# elevator_iopanel_revA.net
KiCad netlist of a schematic drawn in EAGLE
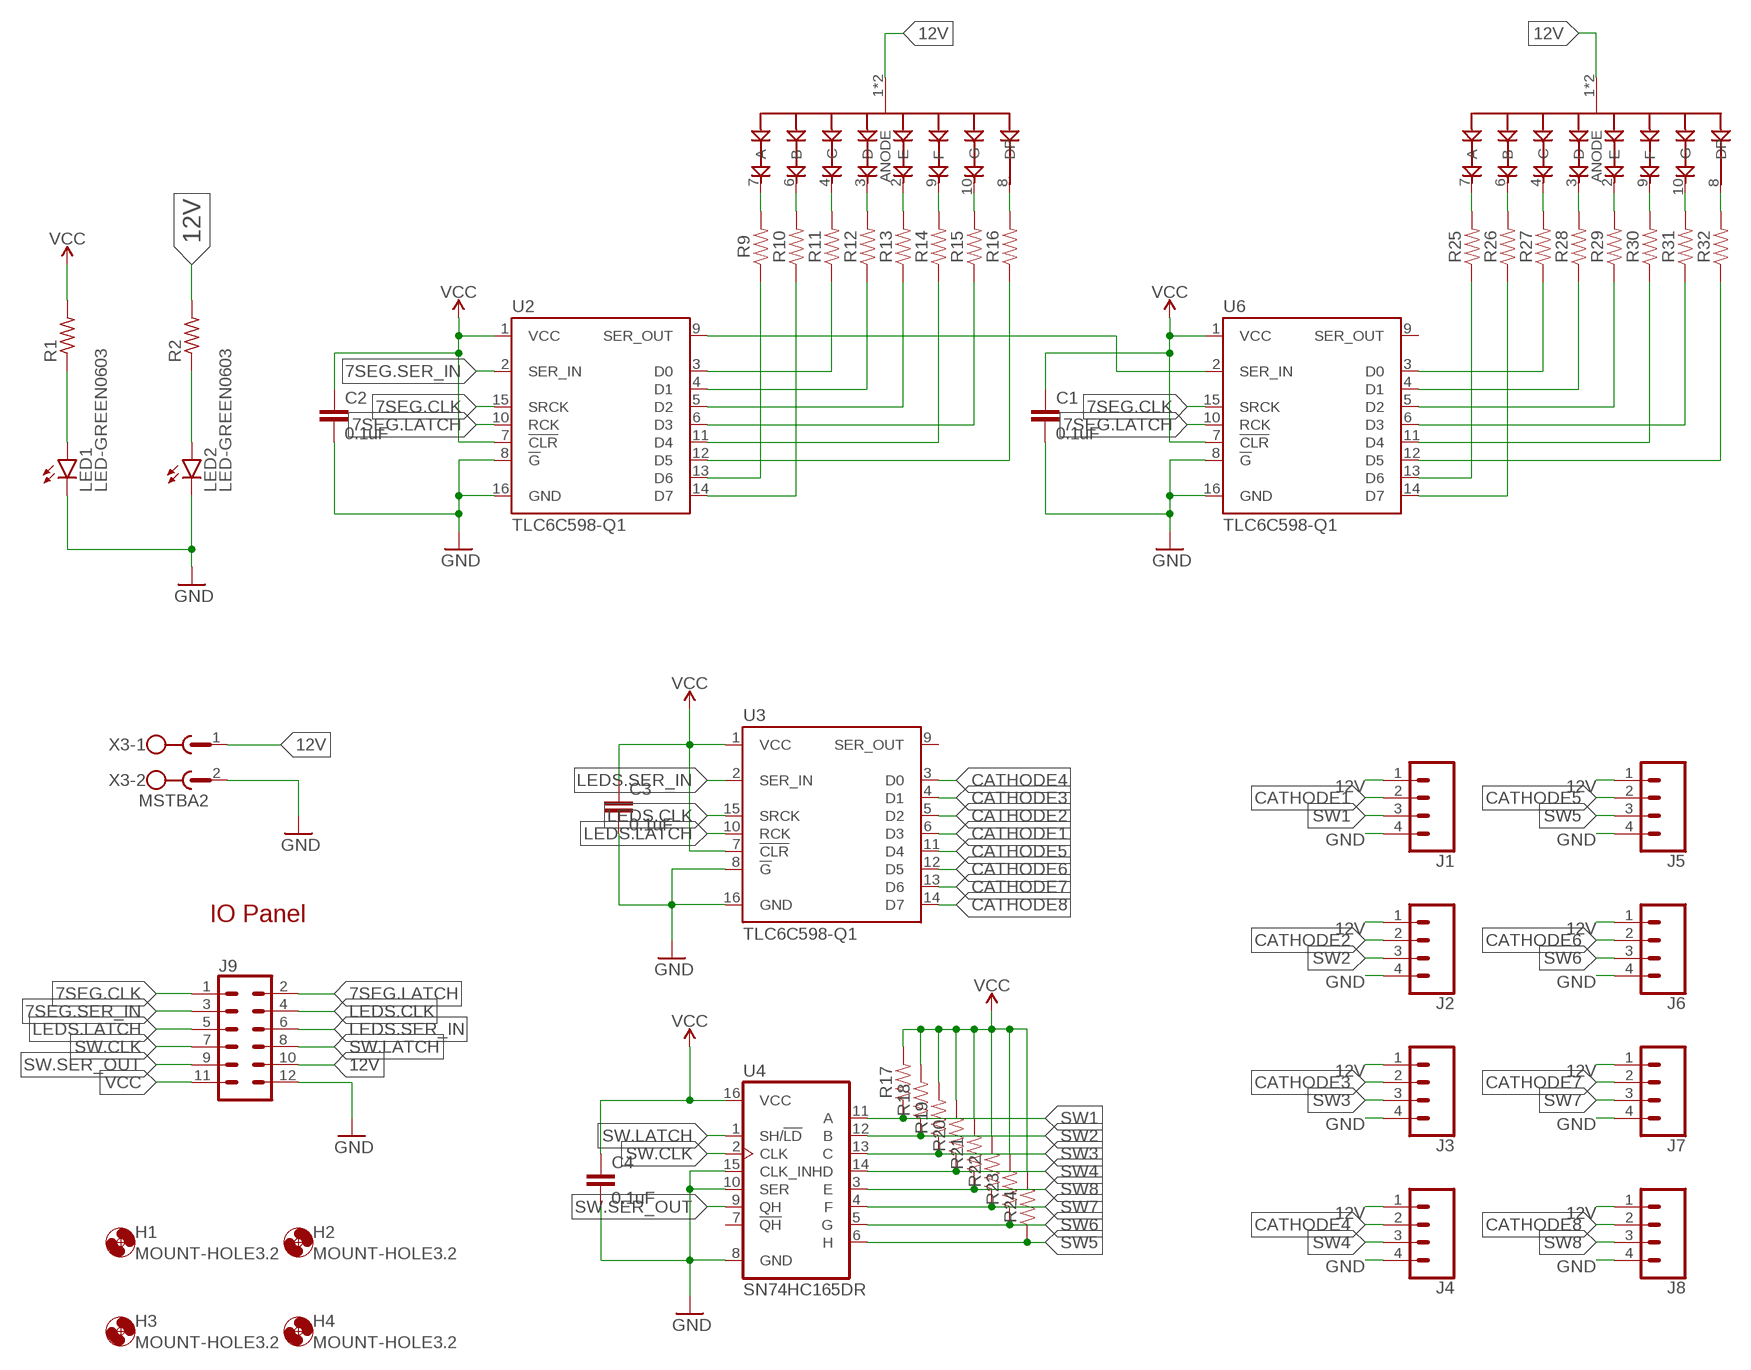
[diagram p0: schematic, sheet 1]

(export (version "E")
  (design (tool "Eeschema 10.0.6"))
  (components
    (comp (ref "C1")
      (value "0.1uF")
      (footprint "eagle-import:0603")
      (libsource (lib "eagle-import") (part "0.1UF-0603-25V-5%"))
    )
    (comp (ref "C2")
      (value "0.1uF")
      (footprint "eagle-import:0603")
      (libsource (lib "eagle-import") (part "0.1UF-0603-25V-5%"))
    )
    (comp (ref "C3")
      (value "0.1uF")
      (footprint "eagle-import:0603")
      (libsource (lib "eagle-import") (part "0.1UF-0603-25V-5%"))
    )
    (comp (ref "C4")
      (value "0.1uF")
      (footprint "eagle-import:0603")
      (libsource (lib "eagle-import") (part "0.1UF-0603-25V-5%"))
    )
    (comp (ref "D2")
      (value "SA15-11EWA")
      (footprint "eagle-import:SA15-11EWA")
      (libsource (lib "eagle-import") (part "SA15-11EWA"))
    )
    (comp (ref "D4")
      (value "SA15-11EWA")
      (footprint "eagle-import:SA15-11EWA")
      (libsource (lib "eagle-import") (part "SA15-11EWA"))
    )
    (comp (ref "H1")
      (value "MOUNT-HOLE3.2")
      (footprint "eagle-import:3,2")
      (libsource (lib "eagle-import") (part "MOUNT-HOLE3.2"))
    )
    (comp (ref "H2")
      (value "MOUNT-HOLE3.2")
      (footprint "eagle-import:3,2")
      (libsource (lib "eagle-import") (part "MOUNT-HOLE3.2"))
    )
    (comp (ref "H3")
      (value "MOUNT-HOLE3.2")
      (footprint "eagle-import:3,2")
      (libsource (lib "eagle-import") (part "MOUNT-HOLE3.2"))
    )
    (comp (ref "H4")
      (value "MOUNT-HOLE3.2")
      (footprint "eagle-import:3,2")
      (libsource (lib "eagle-import") (part "MOUNT-HOLE3.2"))
    )
    (comp (ref "J1")
      (value "CONN_04LONGPADS")
      (footprint "eagle-import:1X04_LONGPADS")
      (libsource (lib "eagle-import") (part "CONN_04LONGPADS"))
    )
    (comp (ref "J2")
      (value "CONN_04LONGPADS")
      (footprint "eagle-import:1X04_LONGPADS")
      (libsource (lib "eagle-import") (part "CONN_04LONGPADS"))
    )
    (comp (ref "J3")
      (value "CONN_04LONGPADS")
      (footprint "eagle-import:1X04_LONGPADS")
      (libsource (lib "eagle-import") (part "CONN_04LONGPADS"))
    )
    (comp (ref "J4")
      (value "CONN_04LONGPADS")
      (footprint "eagle-import:1X04_LONGPADS")
      (libsource (lib "eagle-import") (part "CONN_04LONGPADS"))
    )
    (comp (ref "J5")
      (value "CONN_04LONGPADS")
      (footprint "eagle-import:1X04_LONGPADS")
      (libsource (lib "eagle-import") (part "CONN_04LONGPADS"))
    )
    (comp (ref "J6")
      (value "CONN_04LONGPADS")
      (footprint "eagle-import:1X04_LONGPADS")
      (libsource (lib "eagle-import") (part "CONN_04LONGPADS"))
    )
    (comp (ref "J7")
      (value "CONN_04LONGPADS")
      (footprint "eagle-import:1X04_LONGPADS")
      (libsource (lib "eagle-import") (part "CONN_04LONGPADS"))
    )
    (comp (ref "J8")
      (value "CONN_04LONGPADS")
      (footprint "eagle-import:1X04_LONGPADS")
      (libsource (lib "eagle-import") (part "CONN_04LONGPADS"))
    )
    (comp (ref "J9")
      (value "CONN_06X22X6SHR")
      (footprint "eagle-import:2X6-SHROUDED")
      (libsource (lib "eagle-import") (part "CONN_06X22X6SHR"))
    )
    (comp (ref "LED1")
      (value "LED-GREEN0603")
      (footprint "eagle-import:0603-GREEN")
      (libsource (lib "eagle-import") (part "LED-GREEN0603"))
    )
    (comp (ref "LED2")
      (value "LED-GREEN0603")
      (footprint "eagle-import:0603-GREEN")
      (libsource (lib "eagle-import") (part "LED-GREEN0603"))
    )
    (comp (ref "R1")
      (value "R-US_R0603")
      (footprint "eagle-import:R0603")
      (libsource (lib "eagle-import") (part "R-US_R0603"))
    )
    (comp (ref "R2")
      (value "R-US_R0603")
      (footprint "eagle-import:R0603")
      (libsource (lib "eagle-import") (part "R-US_R0603"))
    )
    (comp (ref "R9")
      (value "20KOHM-0603-1/10W-1%")
      (footprint "eagle-import:0603")
      (libsource (lib "eagle-import") (part "20KOHM-0603-1/10W-1%"))
    )
    (comp (ref "R10")
      (value "20KOHM-0603-1/10W-1%")
      (footprint "eagle-import:0603")
      (libsource (lib "eagle-import") (part "20KOHM-0603-1/10W-1%"))
    )
    (comp (ref "R11")
      (value "20KOHM-0603-1/10W-1%")
      (footprint "eagle-import:0603")
      (libsource (lib "eagle-import") (part "20KOHM-0603-1/10W-1%"))
    )
    (comp (ref "R12")
      (value "20KOHM-0603-1/10W-1%")
      (footprint "eagle-import:0603")
      (libsource (lib "eagle-import") (part "20KOHM-0603-1/10W-1%"))
    )
    (comp (ref "R13")
      (value "20KOHM-0603-1/10W-1%")
      (footprint "eagle-import:0603")
      (libsource (lib "eagle-import") (part "20KOHM-0603-1/10W-1%"))
    )
    (comp (ref "R14")
      (value "20KOHM-0603-1/10W-1%")
      (footprint "eagle-import:0603")
      (libsource (lib "eagle-import") (part "20KOHM-0603-1/10W-1%"))
    )
    (comp (ref "R15")
      (value "20KOHM-0603-1/10W-1%")
      (footprint "eagle-import:0603")
      (libsource (lib "eagle-import") (part "20KOHM-0603-1/10W-1%"))
    )
    (comp (ref "R16")
      (value "20KOHM-0603-1/10W-1%")
      (footprint "eagle-import:0603")
      (libsource (lib "eagle-import") (part "20KOHM-0603-1/10W-1%"))
    )
    (comp (ref "R17")
      (value "20KOHM-0603-1/10W-1%")
      (footprint "eagle-import:0603")
      (libsource (lib "eagle-import") (part "20KOHM-0603-1/10W-1%"))
    )
    (comp (ref "R18")
      (value "20KOHM-0603-1/10W-1%")
      (footprint "eagle-import:0603")
      (libsource (lib "eagle-import") (part "20KOHM-0603-1/10W-1%"))
    )
    (comp (ref "R19")
      (value "20KOHM-0603-1/10W-1%")
      (footprint "eagle-import:0603")
      (libsource (lib "eagle-import") (part "20KOHM-0603-1/10W-1%"))
    )
    (comp (ref "R20")
      (value "20KOHM-0603-1/10W-1%")
      (footprint "eagle-import:0603")
      (libsource (lib "eagle-import") (part "20KOHM-0603-1/10W-1%"))
    )
    (comp (ref "R21")
      (value "20KOHM-0603-1/10W-1%")
      (footprint "eagle-import:0603")
      (libsource (lib "eagle-import") (part "20KOHM-0603-1/10W-1%"))
    )
    (comp (ref "R22")
      (value "20KOHM-0603-1/10W-1%")
      (footprint "eagle-import:0603")
      (libsource (lib "eagle-import") (part "20KOHM-0603-1/10W-1%"))
    )
    (comp (ref "R23")
      (value "20KOHM-0603-1/10W-1%")
      (footprint "eagle-import:0603")
      (libsource (lib "eagle-import") (part "20KOHM-0603-1/10W-1%"))
    )
    (comp (ref "R24")
      (value "20KOHM-0603-1/10W-1%")
      (footprint "eagle-import:0603")
      (libsource (lib "eagle-import") (part "20KOHM-0603-1/10W-1%"))
    )
    (comp (ref "R25")
      (value "20KOHM-0603-1/10W-1%")
      (footprint "eagle-import:0603")
      (libsource (lib "eagle-import") (part "20KOHM-0603-1/10W-1%"))
    )
    (comp (ref "R26")
      (value "20KOHM-0603-1/10W-1%")
      (footprint "eagle-import:0603")
      (libsource (lib "eagle-import") (part "20KOHM-0603-1/10W-1%"))
    )
    (comp (ref "R27")
      (value "20KOHM-0603-1/10W-1%")
      (footprint "eagle-import:0603")
      (libsource (lib "eagle-import") (part "20KOHM-0603-1/10W-1%"))
    )
    (comp (ref "R28")
      (value "20KOHM-0603-1/10W-1%")
      (footprint "eagle-import:0603")
      (libsource (lib "eagle-import") (part "20KOHM-0603-1/10W-1%"))
    )
    (comp (ref "R29")
      (value "20KOHM-0603-1/10W-1%")
      (footprint "eagle-import:0603")
      (libsource (lib "eagle-import") (part "20KOHM-0603-1/10W-1%"))
    )
    (comp (ref "R30")
      (value "20KOHM-0603-1/10W-1%")
      (footprint "eagle-import:0603")
      (libsource (lib "eagle-import") (part "20KOHM-0603-1/10W-1%"))
    )
    (comp (ref "R31")
      (value "20KOHM-0603-1/10W-1%")
      (footprint "eagle-import:0603")
      (libsource (lib "eagle-import") (part "20KOHM-0603-1/10W-1%"))
    )
    (comp (ref "R32")
      (value "20KOHM-0603-1/10W-1%")
      (footprint "eagle-import:0603")
      (libsource (lib "eagle-import") (part "20KOHM-0603-1/10W-1%"))
    )
    (comp (ref "U2")
      (value "TLC6C598-Q1")
      (footprint "eagle-import:SO16")
      (libsource (lib "eagle-import") (part "TPIC6C596SOIC"))
    )
    (comp (ref "U3")
      (value "TLC6C598-Q1")
      (footprint "eagle-import:SO16")
      (libsource (lib "eagle-import") (part "TPIC6C596SOIC"))
    )
    (comp (ref "U4")
      (value "SN74HC165DR")
      (footprint "eagle-import:SO16")
      (libsource (lib "eagle-import") (part "74165DHC"))
    )
    (comp (ref "U6")
      (value "TLC6C598-Q1")
      (footprint "eagle-import:SO16")
      (libsource (lib "eagle-import") (part "TPIC6C596SOIC"))
    )
    (comp (ref "X3")
      (value "MSTBA2")
      (footprint "eagle-import:MSTBA2")
      (fields (field (name "MF") "FARNELL") (field (name "MPN") "1757242"))
      (libsource (lib "eagle-import") (part "MSTBA2"))
    )
  )
  (nets
    (net (code "1") (name "7SEG.CLK") (class "Default")
      (node (ref "J9") (pin "1") (pinfunction "1_1") (pintype "passive"))
      (node (ref "U2") (pin "15") (pinfunction "SRCK_15") (pintype "input"))
      (node (ref "U6") (pin "15") (pinfunction "SRCK_15") (pintype "input"))
    )
    (net (code "2") (name "7SEG.LATCH") (class "Default")
      (node (ref "J9") (pin "2") (pinfunction "2_2") (pintype "passive"))
      (node (ref "U2") (pin "10") (pinfunction "RCK_10") (pintype "input"))
      (node (ref "U6") (pin "10") (pinfunction "RCK_10") (pintype "input"))
    )
    (net (code "3") (name "7SEG.SER_IN") (class "Default")
      (node (ref "J9") (pin "3") (pinfunction "3_3") (pintype "passive"))
      (node (ref "U2") (pin "2") (pinfunction "SER_IN_2") (pintype "input"))
    )
    (net (code "4") (name "12V") (class "Default")
      (node (ref "D2") (pin "1") (pinfunction "ANODE_1") (pintype "bidirectional"))
      (node (ref "D2") (pin "5") (pinfunction "ANODE_5") (pintype "bidirectional"))
      (node (ref "D4") (pin "1") (pinfunction "ANODE_1") (pintype "bidirectional"))
      (node (ref "D4") (pin "5") (pinfunction "ANODE_5") (pintype "bidirectional"))
      (node (ref "J1") (pin "1") (pinfunction "1_1") (pintype "passive"))
      (node (ref "J2") (pin "1") (pinfunction "1_1") (pintype "passive"))
      (node (ref "J3") (pin "1") (pinfunction "1_1") (pintype "passive"))
      (node (ref "J4") (pin "1") (pinfunction "1_1") (pintype "passive"))
      (node (ref "J5") (pin "1") (pinfunction "1_1") (pintype "passive"))
      (node (ref "J6") (pin "1") (pinfunction "1_1") (pintype "passive"))
      (node (ref "J7") (pin "1") (pinfunction "1_1") (pintype "passive"))
      (node (ref "J8") (pin "1") (pinfunction "1_1") (pintype "passive"))
      (node (ref "J9") (pin "10") (pinfunction "10_10") (pintype "passive"))
      (node (ref "R2") (pin "2") (pinfunction "2_2") (pintype "passive"))
      (node (ref "X3") (pin "1") (pinfunction "1_1") (pintype "passive"))
    )
    (net (code "5") (name "CATHODE1") (class "Default")
      (node (ref "J1") (pin "2") (pinfunction "2_2") (pintype "passive"))
      (node (ref "U3") (pin "6") (pinfunction "D3_6") (pintype "output"))
    )
    (net (code "6") (name "CATHODE2") (class "Default")
      (node (ref "J2") (pin "2") (pinfunction "2_2") (pintype "passive"))
      (node (ref "U3") (pin "5") (pinfunction "D2_5") (pintype "output"))
    )
    (net (code "7") (name "CATHODE3") (class "Default")
      (node (ref "J3") (pin "2") (pinfunction "2_2") (pintype "passive"))
      (node (ref "U3") (pin "4") (pinfunction "D1_4") (pintype "output"))
    )
    (net (code "8") (name "CATHODE4") (class "Default")
      (node (ref "J4") (pin "2") (pinfunction "2_2") (pintype "passive"))
      (node (ref "U3") (pin "3") (pinfunction "D0_3") (pintype "output"))
    )
    (net (code "9") (name "CATHODE5") (class "Default")
      (node (ref "J5") (pin "2") (pinfunction "2_2") (pintype "passive"))
      (node (ref "U3") (pin "11") (pinfunction "D4_11") (pintype "output"))
    )
    (net (code "10") (name "CATHODE6") (class "Default")
      (node (ref "J6") (pin "2") (pinfunction "2_2") (pintype "passive"))
      (node (ref "U3") (pin "12") (pinfunction "D5_12") (pintype "output"))
    )
    (net (code "11") (name "CATHODE7") (class "Default")
      (node (ref "J7") (pin "2") (pinfunction "2_2") (pintype "passive"))
      (node (ref "U3") (pin "13") (pinfunction "D6_13") (pintype "output"))
    )
    (net (code "12") (name "CATHODE8") (class "Default")
      (node (ref "J8") (pin "2") (pinfunction "2_2") (pintype "passive"))
      (node (ref "U3") (pin "14") (pinfunction "D7_14") (pintype "output"))
    )
    (net (code "13") (name "GND") (class "Default")
      (node (ref "C1") (pin "2") (pinfunction "2_2") (pintype "passive"))
      (node (ref "C2") (pin "2") (pinfunction "2_2") (pintype "passive"))
      (node (ref "C3") (pin "2") (pinfunction "2_2") (pintype "passive"))
      (node (ref "C4") (pin "2") (pinfunction "2_2") (pintype "passive"))
      (node (ref "J1") (pin "4") (pinfunction "4_4") (pintype "passive"))
      (node (ref "J2") (pin "4") (pinfunction "4_4") (pintype "passive"))
      (node (ref "J3") (pin "4") (pinfunction "4_4") (pintype "passive"))
      (node (ref "J4") (pin "4") (pinfunction "4_4") (pintype "passive"))
      (node (ref "J5") (pin "4") (pinfunction "4_4") (pintype "passive"))
      (node (ref "J6") (pin "4") (pinfunction "4_4") (pintype "passive"))
      (node (ref "J7") (pin "4") (pinfunction "4_4") (pintype "passive"))
      (node (ref "J8") (pin "4") (pinfunction "4_4") (pintype "passive"))
      (node (ref "J9") (pin "12") (pinfunction "12_12") (pintype "passive"))
      (node (ref "LED1") (pin "C") (pinfunction "C_C") (pintype "passive"))
      (node (ref "LED2") (pin "C") (pinfunction "C_C") (pintype "passive"))
      (node (ref "U2") (pin "16") (pinfunction "GND_16") (pintype "power_in"))
      (node (ref "U2") (pin "8") (pinfunction "~{G}_8") (pintype "input"))
      (node (ref "U3") (pin "16") (pinfunction "GND_16") (pintype "power_in"))
      (node (ref "U3") (pin "8") (pinfunction "~{G}_8") (pintype "input"))
      (node (ref "U4") (pin "10") (pinfunction "SER_10") (pintype "input"))
      (node (ref "U4") (pin "15") (pinfunction "CLK_INH_15") (pintype "input"))
      (node (ref "U4") (pin "8") (pinfunction "GND_8") (pintype "power_in"))
      (node (ref "U6") (pin "16") (pinfunction "GND_16") (pintype "power_in"))
      (node (ref "U6") (pin "8") (pinfunction "~{G}_8") (pintype "input"))
      (node (ref "X3") (pin "2") (pinfunction "1_2") (pintype "passive"))
    )
    (net (code "14") (name "LEDS.CLK") (class "Default")
      (node (ref "J9") (pin "4") (pinfunction "4_4") (pintype "passive"))
      (node (ref "U3") (pin "15") (pinfunction "SRCK_15") (pintype "input"))
    )
    (net (code "15") (name "LEDS.LATCH") (class "Default")
      (node (ref "J9") (pin "5") (pinfunction "5_5") (pintype "passive"))
      (node (ref "U3") (pin "10") (pinfunction "RCK_10") (pintype "input"))
    )
    (net (code "16") (name "LEDS.SER_IN") (class "Default")
      (node (ref "J9") (pin "6") (pinfunction "6_6") (pintype "passive"))
      (node (ref "U3") (pin "2") (pinfunction "SER_IN_2") (pintype "input"))
    )
    (net (code "17") (name "Net-(D2-A)") (class "Default")
      (node (ref "D2") (pin "7") (pinfunction "A_7") (pintype "bidirectional"))
      (node (ref "R9") (pin "2") (pinfunction "2_2") (pintype "passive"))
    )
    (net (code "18") (name "Net-(D2-B)") (class "Default")
      (node (ref "D2") (pin "6") (pinfunction "B_6") (pintype "bidirectional"))
      (node (ref "R10") (pin "2") (pinfunction "2_2") (pintype "passive"))
    )
    (net (code "19") (name "Net-(D2-C)") (class "Default")
      (node (ref "D2") (pin "4") (pinfunction "C_4") (pintype "bidirectional"))
      (node (ref "R11") (pin "2") (pinfunction "2_2") (pintype "passive"))
    )
    (net (code "20") (name "Net-(D2-D)") (class "Default")
      (node (ref "D2") (pin "3") (pinfunction "D_3") (pintype "bidirectional"))
      (node (ref "R12") (pin "2") (pinfunction "2_2") (pintype "passive"))
    )
    (net (code "21") (name "Net-(D2-DP)") (class "Default")
      (node (ref "D2") (pin "8") (pinfunction "DP_8") (pintype "bidirectional"))
      (node (ref "R16") (pin "2") (pinfunction "2_2") (pintype "passive"))
    )
    (net (code "22") (name "Net-(D2-E)") (class "Default")
      (node (ref "D2") (pin "2") (pinfunction "E_2") (pintype "bidirectional"))
      (node (ref "R13") (pin "2") (pinfunction "2_2") (pintype "passive"))
    )
    (net (code "23") (name "Net-(D2-F)") (class "Default")
      (node (ref "D2") (pin "9") (pinfunction "F_9") (pintype "bidirectional"))
      (node (ref "R14") (pin "2") (pinfunction "2_2") (pintype "passive"))
    )
    (net (code "24") (name "Net-(D2-G)") (class "Default")
      (node (ref "D2") (pin "10") (pinfunction "G_10") (pintype "bidirectional"))
      (node (ref "R15") (pin "2") (pinfunction "2_2") (pintype "passive"))
    )
    (net (code "25") (name "Net-(D4-A)") (class "Default")
      (node (ref "D4") (pin "7") (pinfunction "A_7") (pintype "bidirectional"))
      (node (ref "R25") (pin "2") (pinfunction "2_2") (pintype "passive"))
    )
    (net (code "26") (name "Net-(D4-B)") (class "Default")
      (node (ref "D4") (pin "6") (pinfunction "B_6") (pintype "bidirectional"))
      (node (ref "R26") (pin "2") (pinfunction "2_2") (pintype "passive"))
    )
    (net (code "27") (name "Net-(D4-C)") (class "Default")
      (node (ref "D4") (pin "4") (pinfunction "C_4") (pintype "bidirectional"))
      (node (ref "R27") (pin "2") (pinfunction "2_2") (pintype "passive"))
    )
    (net (code "28") (name "Net-(D4-D)") (class "Default")
      (node (ref "D4") (pin "3") (pinfunction "D_3") (pintype "bidirectional"))
      (node (ref "R28") (pin "2") (pinfunction "2_2") (pintype "passive"))
    )
    (net (code "29") (name "Net-(D4-DP)") (class "Default")
      (node (ref "D4") (pin "8") (pinfunction "DP_8") (pintype "bidirectional"))
      (node (ref "R32") (pin "2") (pinfunction "2_2") (pintype "passive"))
    )
    (net (code "30") (name "Net-(D4-E)") (class "Default")
      (node (ref "D4") (pin "2") (pinfunction "E_2") (pintype "bidirectional"))
      (node (ref "R29") (pin "2") (pinfunction "2_2") (pintype "passive"))
    )
    (net (code "31") (name "Net-(D4-F)") (class "Default")
      (node (ref "D4") (pin "9") (pinfunction "F_9") (pintype "bidirectional"))
      (node (ref "R30") (pin "2") (pinfunction "2_2") (pintype "passive"))
    )
    (net (code "32") (name "Net-(D4-G)") (class "Default")
      (node (ref "D4") (pin "10") (pinfunction "G_10") (pintype "bidirectional"))
      (node (ref "R31") (pin "2") (pinfunction "2_2") (pintype "passive"))
    )
    (net (code "33") (name "Net-(LED1-PadA)") (class "Default")
      (node (ref "LED1") (pin "A") (pinfunction "A_A") (pintype "passive"))
      (node (ref "R1") (pin "1") (pinfunction "1_1") (pintype "passive"))
    )
    (net (code "34") (name "Net-(LED2-PadA)") (class "Default")
      (node (ref "LED2") (pin "A") (pinfunction "A_A") (pintype "passive"))
      (node (ref "R2") (pin "1") (pinfunction "1_1") (pintype "passive"))
    )
    (net (code "35") (name "Net-(U2-D0)") (class "Default")
      (node (ref "R11") (pin "1") (pinfunction "1_1") (pintype "passive"))
      (node (ref "U2") (pin "3") (pinfunction "D0_3") (pintype "output"))
    )
    (net (code "36") (name "Net-(U2-D1)") (class "Default")
      (node (ref "R12") (pin "1") (pinfunction "1_1") (pintype "passive"))
      (node (ref "U2") (pin "4") (pinfunction "D1_4") (pintype "output"))
    )
    (net (code "37") (name "Net-(U2-D2)") (class "Default")
      (node (ref "R13") (pin "1") (pinfunction "1_1") (pintype "passive"))
      (node (ref "U2") (pin "5") (pinfunction "D2_5") (pintype "output"))
    )
    (net (code "38") (name "Net-(U2-D3)") (class "Default")
      (node (ref "R15") (pin "1") (pinfunction "1_1") (pintype "passive"))
      (node (ref "U2") (pin "6") (pinfunction "D3_6") (pintype "output"))
    )
    (net (code "39") (name "Net-(U2-D4)") (class "Default")
      (node (ref "R14") (pin "1") (pinfunction "1_1") (pintype "passive"))
      (node (ref "U2") (pin "11") (pinfunction "D4_11") (pintype "output"))
    )
    (net (code "40") (name "Net-(U2-D5)") (class "Default")
      (node (ref "R16") (pin "1") (pinfunction "1_1") (pintype "passive"))
      (node (ref "U2") (pin "12") (pinfunction "D5_12") (pintype "output"))
    )
    (net (code "41") (name "Net-(U2-D6)") (class "Default")
      (node (ref "R9") (pin "1") (pinfunction "1_1") (pintype "passive"))
      (node (ref "U2") (pin "13") (pinfunction "D6_13") (pintype "output"))
    )
    (net (code "42") (name "Net-(U2-D7)") (class "Default")
      (node (ref "R10") (pin "1") (pinfunction "1_1") (pintype "passive"))
      (node (ref "U2") (pin "14") (pinfunction "D7_14") (pintype "output"))
    )
    (net (code "43") (name "Net-(U2-SER_OUT)") (class "Default")
      (node (ref "U2") (pin "9") (pinfunction "SER_OUT_9") (pintype "output"))
      (node (ref "U6") (pin "2") (pinfunction "SER_IN_2") (pintype "input"))
    )
    (net (code "44") (name "Net-(U6-D0)") (class "Default")
      (node (ref "R27") (pin "1") (pinfunction "1_1") (pintype "passive"))
      (node (ref "U6") (pin "3") (pinfunction "D0_3") (pintype "output"))
    )
    (net (code "45") (name "Net-(U6-D1)") (class "Default")
      (node (ref "R28") (pin "1") (pinfunction "1_1") (pintype "passive"))
      (node (ref "U6") (pin "4") (pinfunction "D1_4") (pintype "output"))
    )
    (net (code "46") (name "Net-(U6-D2)") (class "Default")
      (node (ref "R29") (pin "1") (pinfunction "1_1") (pintype "passive"))
      (node (ref "U6") (pin "5") (pinfunction "D2_5") (pintype "output"))
    )
    (net (code "47") (name "Net-(U6-D3)") (class "Default")
      (node (ref "R31") (pin "1") (pinfunction "1_1") (pintype "passive"))
      (node (ref "U6") (pin "6") (pinfunction "D3_6") (pintype "output"))
    )
    (net (code "48") (name "Net-(U6-D4)") (class "Default")
      (node (ref "R30") (pin "1") (pinfunction "1_1") (pintype "passive"))
      (node (ref "U6") (pin "11") (pinfunction "D4_11") (pintype "output"))
    )
    (net (code "49") (name "Net-(U6-D5)") (class "Default")
      (node (ref "R32") (pin "1") (pinfunction "1_1") (pintype "passive"))
      (node (ref "U6") (pin "12") (pinfunction "D5_12") (pintype "output"))
    )
    (net (code "50") (name "Net-(U6-D6)") (class "Default")
      (node (ref "R25") (pin "1") (pinfunction "1_1") (pintype "passive"))
      (node (ref "U6") (pin "13") (pinfunction "D6_13") (pintype "output"))
    )
    (net (code "51") (name "Net-(U6-D7)") (class "Default")
      (node (ref "R26") (pin "1") (pinfunction "1_1") (pintype "passive"))
      (node (ref "U6") (pin "14") (pinfunction "D7_14") (pintype "output"))
    )
    (net (code "52") (name "SW.CLK") (class "Default")
      (node (ref "J9") (pin "7") (pinfunction "7_7") (pintype "passive"))
      (node (ref "U4") (pin "2") (pinfunction "CLK_2") (pintype "input"))
    )
    (net (code "53") (name "SW.LATCH") (class "Default")
      (node (ref "J9") (pin "8") (pinfunction "8_8") (pintype "passive"))
      (node (ref "U4") (pin "1") (pinfunction "SH/~{LD}_1") (pintype "input"))
    )
    (net (code "54") (name "SW.SER_OUT") (class "Default")
      (node (ref "J9") (pin "9") (pinfunction "9_9") (pintype "passive"))
      (node (ref "U4") (pin "9") (pinfunction "QH_9") (pintype "tri_state"))
    )
    (net (code "55") (name "SW1") (class "Default")
      (node (ref "J1") (pin "3") (pinfunction "3_3") (pintype "passive"))
      (node (ref "R17") (pin "1") (pinfunction "1_1") (pintype "passive"))
      (node (ref "U4") (pin "11") (pinfunction "A_11") (pintype "tri_state"))
    )
    (net (code "56") (name "SW2") (class "Default")
      (node (ref "J2") (pin "3") (pinfunction "3_3") (pintype "passive"))
      (node (ref "R18") (pin "1") (pinfunction "1_1") (pintype "passive"))
      (node (ref "U4") (pin "12") (pinfunction "B_12") (pintype "tri_state"))
    )
    (net (code "57") (name "SW3") (class "Default")
      (node (ref "J3") (pin "3") (pinfunction "3_3") (pintype "passive"))
      (node (ref "R19") (pin "1") (pinfunction "1_1") (pintype "passive"))
      (node (ref "U4") (pin "13") (pinfunction "C_13") (pintype "tri_state"))
    )
    (net (code "58") (name "SW4") (class "Default")
      (node (ref "J4") (pin "3") (pinfunction "3_3") (pintype "passive"))
      (node (ref "R20") (pin "1") (pinfunction "1_1") (pintype "passive"))
      (node (ref "U4") (pin "14") (pinfunction "D_14") (pintype "tri_state"))
    )
    (net (code "59") (name "SW5") (class "Default")
      (node (ref "J5") (pin "3") (pinfunction "3_3") (pintype "passive"))
      (node (ref "R24") (pin "1") (pinfunction "1_1") (pintype "passive"))
      (node (ref "U4") (pin "6") (pinfunction "H_6") (pintype "tri_state"))
    )
    (net (code "60") (name "SW6") (class "Default")
      (node (ref "J6") (pin "3") (pinfunction "3_3") (pintype "passive"))
      (node (ref "R23") (pin "1") (pinfunction "1_1") (pintype "passive"))
      (node (ref "U4") (pin "5") (pinfunction "G_5") (pintype "tri_state"))
    )
    (net (code "61") (name "SW7") (class "Default")
      (node (ref "J7") (pin "3") (pinfunction "3_3") (pintype "passive"))
      (node (ref "R22") (pin "1") (pinfunction "1_1") (pintype "passive"))
      (node (ref "U4") (pin "4") (pinfunction "F_4") (pintype "tri_state"))
    )
    (net (code "62") (name "SW8") (class "Default")
      (node (ref "J8") (pin "3") (pinfunction "3_3") (pintype "passive"))
      (node (ref "R21") (pin "1") (pinfunction "1_1") (pintype "passive"))
      (node (ref "U4") (pin "3") (pinfunction "E_3") (pintype "tri_state"))
    )
    (net (code "63") (name "VCC") (class "Default")
      (node (ref "C1") (pin "1") (pinfunction "1_1") (pintype "passive"))
      (node (ref "C2") (pin "1") (pinfunction "1_1") (pintype "passive"))
      (node (ref "C3") (pin "1") (pinfunction "1_1") (pintype "passive"))
      (node (ref "C4") (pin "1") (pinfunction "1_1") (pintype "passive"))
      (node (ref "J9") (pin "11") (pinfunction "11_11") (pintype "passive"))
      (node (ref "R1") (pin "2") (pinfunction "2_2") (pintype "passive"))
      (node (ref "R17") (pin "2") (pinfunction "2_2") (pintype "passive"))
      (node (ref "R18") (pin "2") (pinfunction "2_2") (pintype "passive"))
      (node (ref "R19") (pin "2") (pinfunction "2_2") (pintype "passive"))
      (node (ref "R20") (pin "2") (pinfunction "2_2") (pintype "passive"))
      (node (ref "R21") (pin "2") (pinfunction "2_2") (pintype "passive"))
      (node (ref "R22") (pin "2") (pinfunction "2_2") (pintype "passive"))
      (node (ref "R23") (pin "2") (pinfunction "2_2") (pintype "passive"))
      (node (ref "R24") (pin "2") (pinfunction "2_2") (pintype "passive"))
      (node (ref "U2") (pin "1") (pinfunction "VCC_1") (pintype "power_in"))
      (node (ref "U2") (pin "7") (pinfunction "~{CLR}_7") (pintype "input"))
      (node (ref "U3") (pin "1") (pinfunction "VCC_1") (pintype "power_in"))
      (node (ref "U3") (pin "7") (pinfunction "~{CLR}_7") (pintype "input"))
      (node (ref "U4") (pin "16") (pinfunction "VCC_16") (pintype "power_in"))
      (node (ref "U6") (pin "1") (pinfunction "VCC_1") (pintype "power_in"))
      (node (ref "U6") (pin "7") (pinfunction "~{CLR}_7") (pintype "input"))
    )
    (net (code "64") (name "unconnected-(U3-SER_OUT-Pad9)") (class "Default")
      (node (ref "U3") (pin "9") (pinfunction "SER_OUT_9") (pintype "output"))
    )
    (net (code "65") (name "unconnected-(U4-~{QH}-Pad7)") (class "Default")
      (node (ref "U4") (pin "7") (pinfunction "~{QH}_7") (pintype "input"))
    )
    (net (code "66") (name "unconnected-(U6-SER_OUT-Pad9)") (class "Default")
      (node (ref "U6") (pin "9") (pinfunction "SER_OUT_9") (pintype "output"))
    )
  )
)
